# led_brick.net
KiCad netlist of a schematic drawn in EAGLE
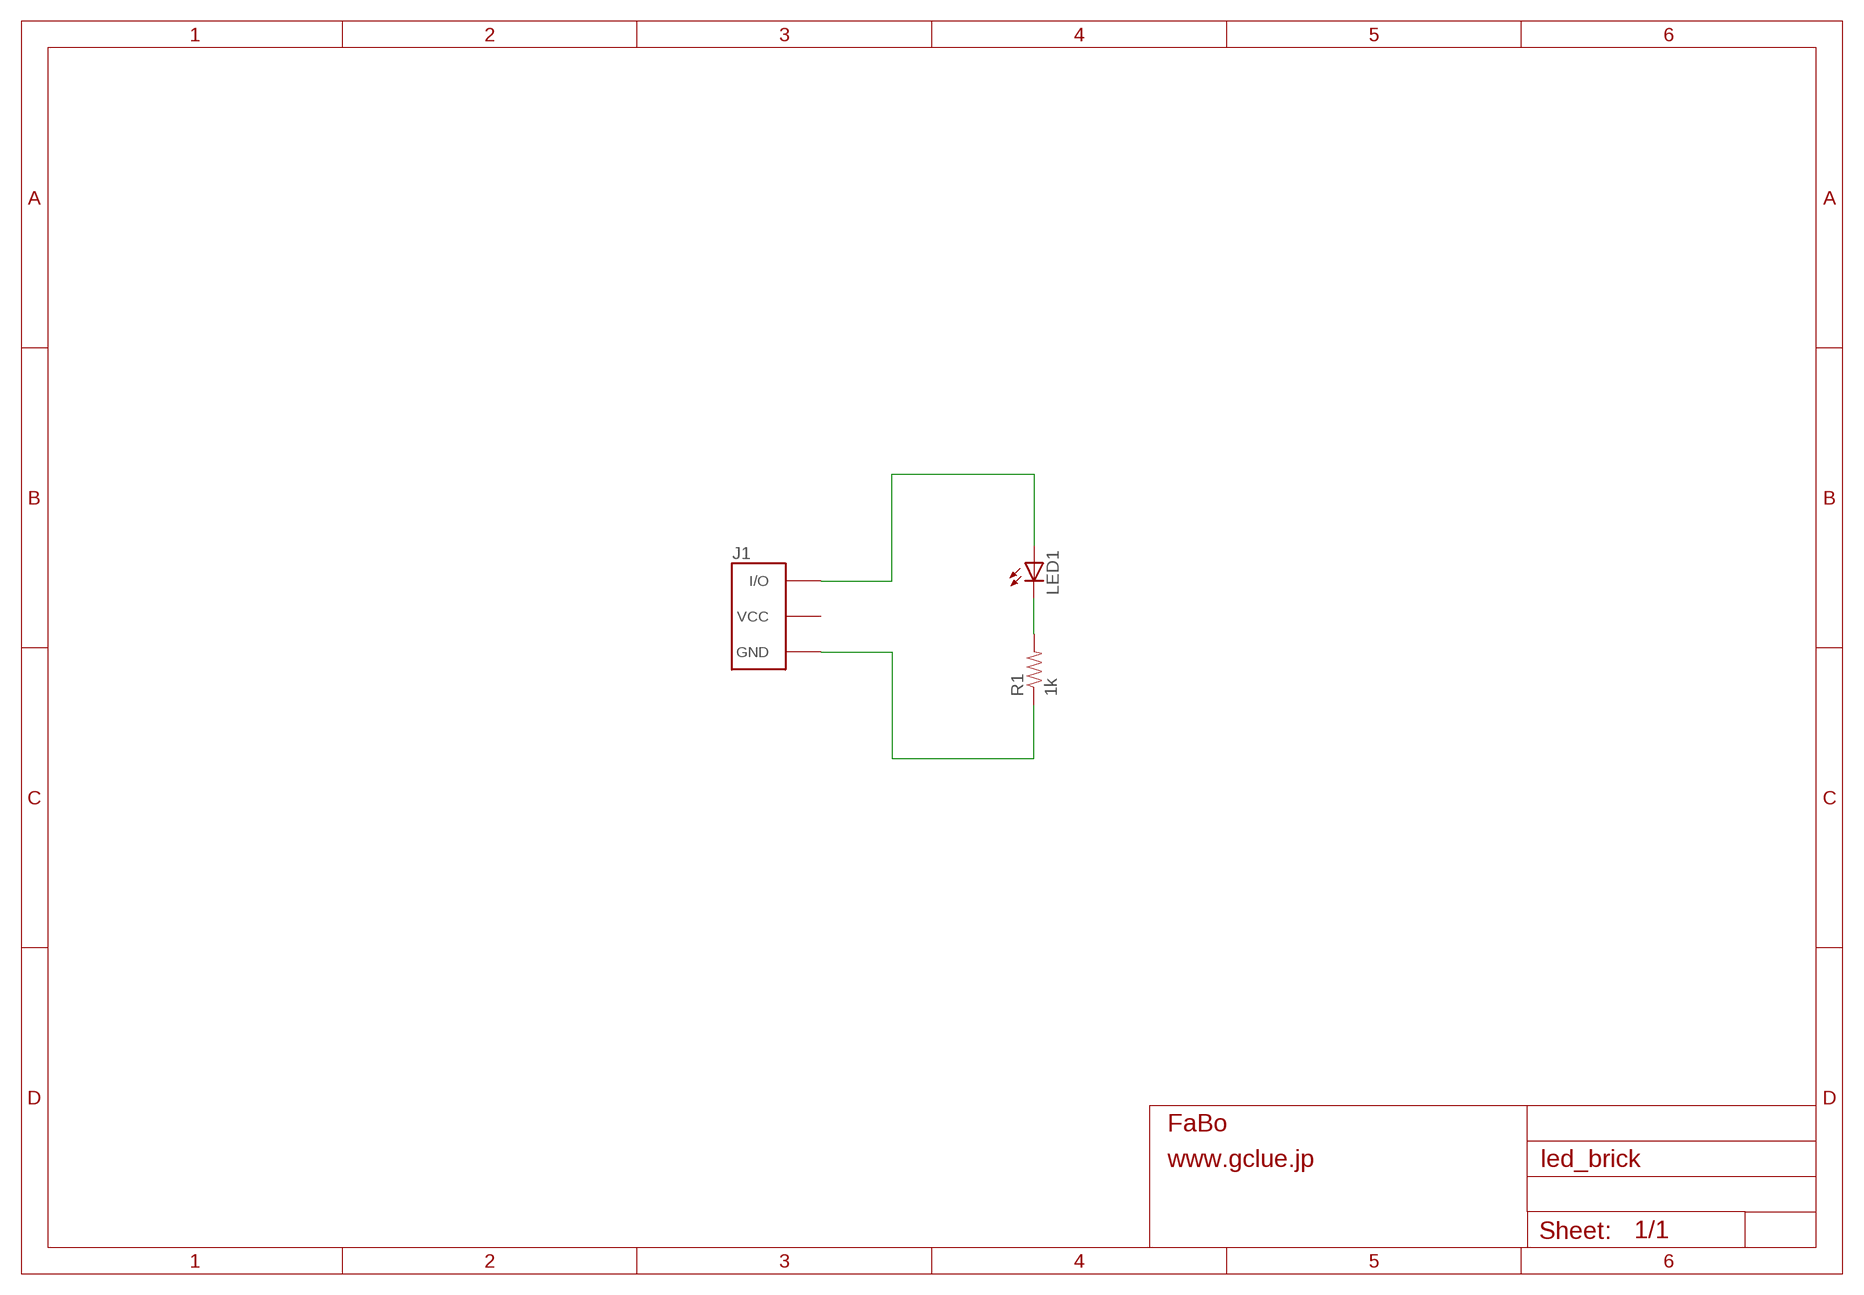
[diagram p0: schematic, sheet 1]

(export (version "E")
  (design (tool "Eeschema 10.0.6"))
  (components
    (comp (ref "J1")
      (value "BRICK_3PIN")
      (footprint "eagle-import:BRICK_3PIN")
      (libsource (lib "eagle-import") (part "BRICK_3PIN"))
    )
    (comp (ref "LED1")
      (value "LED5MM")
      (footprint "eagle-import:LED5MM")
      (libsource (lib "eagle-import") (part "LED5MM"))
    )
    (comp (ref "R1")
      (value "1k")
      (footprint "eagle-import:AXIAL-0.4")
      (libsource (lib "eagle-import") (part "RESISTORPTH-1/4W"))
    )
  )
  (nets
    (net (code "1") (name "Net-(J1-I{slash}O)") (class "Default")
      (node (ref "J1") (pin "IN/OUT") (pinfunction "I/O_IN/OUT") (pintype "bidirectional"))
      (node (ref "LED1") (pin "A") (pinfunction "A_A") (pintype "passive"))
    )
    (net (code "2") (name "Net-(LED1-C)") (class "Default")
      (node (ref "LED1") (pin "K") (pinfunction "C_K") (pintype "passive"))
      (node (ref "R1") (pin "P$2") (pinfunction "2_P$2") (pintype "passive"))
    )
    (net (code "3") (name "Net-(R1-1)") (class "Default")
      (node (ref "J1") (pin "GND") (pinfunction "GND_GND") (pintype "bidirectional"))
      (node (ref "R1") (pin "P$1") (pinfunction "1_P$1") (pintype "passive"))
    )
    (net (code "4") (name "unconnected-(J1-PadVCC)") (class "Default")
      (node (ref "J1") (pin "VCC") (pinfunction "VCC_VCC") (pintype "bidirectional"))
    )
  )
)
